# exBoard_2.net
KiCad netlist of a schematic drawn in EasyEDA Pro
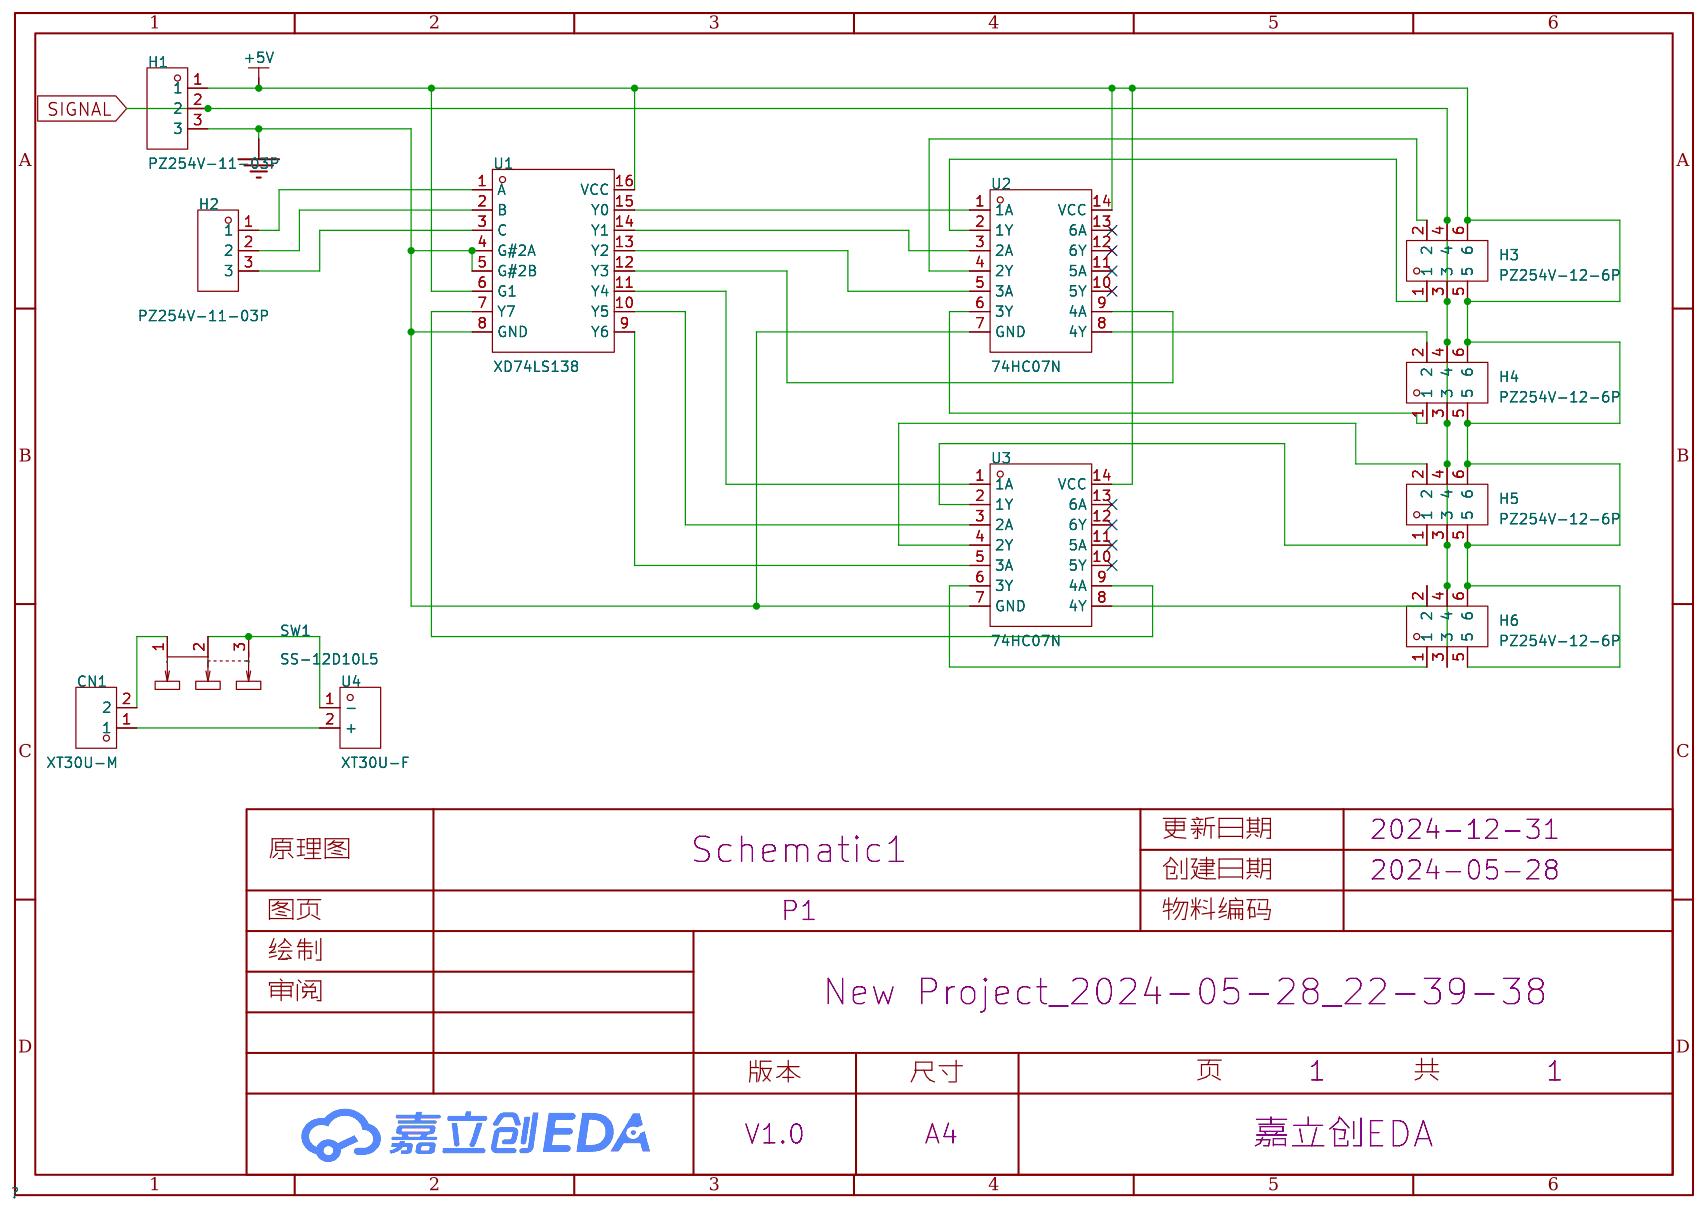
[diagram p0: schematic sheet]

(export (version "E")
  (design (tool "Eeschema 10.0.6"))
  (components
    (comp (ref "CN1")
      (value "XT30U-M")
      (footprint "easyedapro:CONN-TH_XT30U-M")
      (description "类别:-;类型1:-;")
      (fields (field (name "Manufacturer") "AMASS(艾迈斯)"))
      (libsource (lib "easyedapro") (part "XT30U-M"))
    )
    (comp (ref "H1")
      (value "PZ254V-11-03P")
      (footprint "easyedapro:HDR-TH_3P-P2.54-V-M")
      (fields (field (name "Manufacturer") "XFCN(兴飞)"))
      (libsource (lib "easyedapro") (part "PZ254V-11-03P_C2937625"))
    )
    (comp (ref "H2")
      (value "PZ254V-11-03P")
      (footprint "easyedapro:HDR-TH_3P-P2.54-V-M")
      (fields (field (name "Manufacturer") "XFCN(兴飞)"))
      (libsource (lib "easyedapro") (part "PZ254V-11-03P_C2937625"))
    )
    (comp (ref "H3")
      (value "PZ254V-12-6P")
      (footprint "easyedapro:HDR-TH_6P-P2.54-V-M-R2-C3-S2.54")
      (fields (field (name "Manufacturer") "XFCN(兴飞)"))
      (libsource (lib "easyedapro") (part "PZ254V-12-6P"))
    )
    (comp (ref "H4")
      (value "PZ254V-12-6P")
      (footprint "easyedapro:HDR-TH_6P-P2.54-V-M-R2-C3-S2.54")
      (fields (field (name "Manufacturer") "XFCN(兴飞)"))
      (libsource (lib "easyedapro") (part "PZ254V-12-6P"))
    )
    (comp (ref "H5")
      (value "PZ254V-12-6P")
      (footprint "easyedapro:HDR-TH_6P-P2.54-V-M-R2-C3-S2.54")
      (fields (field (name "Manufacturer") "XFCN(兴飞)"))
      (libsource (lib "easyedapro") (part "PZ254V-12-6P"))
    )
    (comp (ref "H6")
      (value "PZ254V-12-6P")
      (footprint "easyedapro:HDR-TH_6P-P2.54-V-M-R2-C3-S2.54")
      (fields (field (name "Manufacturer") "XFCN(兴飞)"))
      (libsource (lib "easyedapro") (part "PZ254V-12-6P"))
    )
    (comp (ref "SW1")
      (value "SS-12D10L5")
      (footprint "easyedapro:SW-TH_SS-12D10L5")
      (description "电路结构:单刀双掷;安装方式:直插;开关颜色:黑色;额定电流(DC):3A;额定电压(DC):125V;额定电流(AC):3A;额定电压(AC):125V;机械寿命:1万次;")
      (fields (field (name "Manufacturer") "XKB Connectivity(中国星坤)"))
      (libsource (lib "easyedapro") (part "SS-12D10L5"))
    )
    (comp (ref "U1")
      (value "XD74LS138")
      (footprint "easyedapro:DIP-16_L19.8-W6.5-P2.54-LS7.6-BL")
      (description "解码器/多路解器 低电平输出电流(IOL)：8mA 高电平输出电流(IOH)：400uA 供电电源：单电源 供电电压：4.75V~5.25V 3 线路到")
      (fields (field (name "Manufacturer") "XINLUDA(信路达)"))
      (libsource (lib "easyedapro") (part "XD74LS138"))
    )
    (comp (ref "U2")
      (value "74HC07N")
      (footprint "easyedapro:DIP-14_L19.4-W6.4-P2.54-LS7.6-BL")
      (fields (field (name "Manufacturer") "HGSEMI(华冠)"))
      (libsource (lib "easyedapro") (part "74HC07N"))
    )
    (comp (ref "U3")
      (value "74HC07N")
      (footprint "easyedapro:DIP-14_L19.4-W6.4-P2.54-LS7.6-BL")
      (fields (field (name "Manufacturer") "HGSEMI(华冠)"))
      (libsource (lib "easyedapro") (part "74HC07N"))
    )
    (comp (ref "U4")
      (value "XT30U-F")
      (footprint "easyedapro:CONN-TH_XT30U-F")
      (description "类别:-;类型1:-;")
      (fields (field (name "Manufacturer") "AMASS(艾迈斯)"))
      (libsource (lib "easyedapro") (part "XT30U-F"))
    )
  )
  (nets
    (net (code "1") (name "+5V") (class "Default")
      (node (ref "H1") (pin "1") (pinfunction "1_1") (pintype "unspecified"))
      (node (ref "H3") (pin "5") (pinfunction "5_5") (pintype "unspecified"))
      (node (ref "H3") (pin "6") (pinfunction "6_6") (pintype "unspecified"))
      (node (ref "H4") (pin "5") (pinfunction "5_5") (pintype "unspecified"))
      (node (ref "H4") (pin "6") (pinfunction "6_6") (pintype "unspecified"))
      (node (ref "H5") (pin "5") (pinfunction "5_5") (pintype "unspecified"))
      (node (ref "H5") (pin "6") (pinfunction "6_6") (pintype "unspecified"))
      (node (ref "H6") (pin "5") (pinfunction "5_5") (pintype "unspecified"))
      (node (ref "H6") (pin "6") (pinfunction "6_6") (pintype "unspecified"))
      (node (ref "U1") (pin "16") (pinfunction "VCC_16") (pintype "unspecified"))
      (node (ref "U1") (pin "6") (pinfunction "G1_6") (pintype "unspecified"))
      (node (ref "U2") (pin "14") (pinfunction "VCC_14") (pintype "unspecified"))
      (node (ref "U3") (pin "14") (pinfunction "VCC_14") (pintype "unspecified"))
    )
    (net (code "2") (name "GND") (class "Default")
      (node (ref "H1") (pin "3") (pinfunction "3_3") (pintype "unspecified"))
      (node (ref "U1") (pin "4") (pinfunction "G#2A_4") (pintype "unspecified"))
      (node (ref "U1") (pin "5") (pinfunction "G#2B_5") (pintype "unspecified"))
      (node (ref "U1") (pin "8") (pinfunction "GND_8") (pintype "unspecified"))
      (node (ref "U2") (pin "7") (pinfunction "GND_7") (pintype "unspecified"))
      (node (ref "U3") (pin "7") (pinfunction "GND_7") (pintype "unspecified"))
    )
    (net (code "3") (name "Net-(CN1-Pad2)") (class "Default")
      (node (ref "CN1") (pin "2") (pinfunction "2_2") (pintype "input"))
      (node (ref "SW1") (pin "1") (pinfunction "1_1") (pintype "unspecified"))
    )
    (net (code "4") (name "Net-(U1-A)") (class "Default")
      (node (ref "H2") (pin "1") (pinfunction "1_1") (pintype "unspecified"))
      (node (ref "U1") (pin "1") (pinfunction "A_1") (pintype "unspecified"))
    )
    (net (code "5") (name "Net-(U1-B)") (class "Default")
      (node (ref "H2") (pin "2") (pinfunction "2_2") (pintype "unspecified"))
      (node (ref "U1") (pin "2") (pinfunction "B_2") (pintype "unspecified"))
    )
    (net (code "6") (name "Net-(U1-C)") (class "Default")
      (node (ref "H2") (pin "3") (pinfunction "3_3") (pintype "unspecified"))
      (node (ref "U1") (pin "3") (pinfunction "C_3") (pintype "unspecified"))
    )
    (net (code "7") (name "Net-(U1-Y0)") (class "Default")
      (node (ref "U1") (pin "15") (pinfunction "Y0_15") (pintype "unspecified"))
      (node (ref "U2") (pin "1") (pinfunction "1A_1") (pintype "unspecified"))
    )
    (net (code "8") (name "Net-(U1-Y1)") (class "Default")
      (node (ref "U1") (pin "14") (pinfunction "Y1_14") (pintype "unspecified"))
      (node (ref "U2") (pin "3") (pinfunction "2A_3") (pintype "unspecified"))
    )
    (net (code "9") (name "Net-(U1-Y2)") (class "Default")
      (node (ref "U1") (pin "13") (pinfunction "Y2_13") (pintype "unspecified"))
      (node (ref "U2") (pin "5") (pinfunction "3A_5") (pintype "unspecified"))
    )
    (net (code "10") (name "Net-(U1-Y3)") (class "Default")
      (node (ref "U1") (pin "12") (pinfunction "Y3_12") (pintype "unspecified"))
      (node (ref "U2") (pin "9") (pinfunction "4A_9") (pintype "unspecified"))
    )
    (net (code "11") (name "Net-(U1-Y4)") (class "Default")
      (node (ref "U1") (pin "11") (pinfunction "Y4_11") (pintype "unspecified"))
      (node (ref "U3") (pin "1") (pinfunction "1A_1") (pintype "unspecified"))
    )
    (net (code "12") (name "Net-(U1-Y5)") (class "Default")
      (node (ref "U1") (pin "10") (pinfunction "Y5_10") (pintype "unspecified"))
      (node (ref "U3") (pin "3") (pinfunction "2A_3") (pintype "unspecified"))
    )
    (net (code "13") (name "Net-(U1-Y6)") (class "Default")
      (node (ref "U1") (pin "9") (pinfunction "Y6_9") (pintype "unspecified"))
      (node (ref "U3") (pin "5") (pinfunction "3A_5") (pintype "unspecified"))
    )
    (net (code "14") (name "Net-(U1-Y7)") (class "Default")
      (node (ref "U1") (pin "7") (pinfunction "Y7_7") (pintype "unspecified"))
      (node (ref "U3") (pin "9") (pinfunction "4A_9") (pintype "unspecified"))
    )
    (net (code "15") (name "Net-(U2-1Y)") (class "Default")
      (node (ref "H3") (pin "1") (pinfunction "1_1") (pintype "unspecified"))
      (node (ref "U2") (pin "2") (pinfunction "1Y_2") (pintype "unspecified"))
    )
    (net (code "16") (name "Net-(U2-2Y)") (class "Default")
      (node (ref "H3") (pin "2") (pinfunction "2_2") (pintype "unspecified"))
      (node (ref "U2") (pin "4") (pinfunction "2Y_4") (pintype "unspecified"))
    )
    (net (code "17") (name "Net-(U2-3Y)") (class "Default")
      (node (ref "H4") (pin "1") (pinfunction "1_1") (pintype "unspecified"))
      (node (ref "U2") (pin "6") (pinfunction "3Y_6") (pintype "unspecified"))
    )
    (net (code "18") (name "Net-(U2-4Y)") (class "Default")
      (node (ref "H4") (pin "2") (pinfunction "2_2") (pintype "unspecified"))
      (node (ref "U2") (pin "8") (pinfunction "4Y_8") (pintype "unspecified"))
    )
    (net (code "19") (name "Net-(U3-1Y)") (class "Default")
      (node (ref "H5") (pin "1") (pinfunction "1_1") (pintype "unspecified"))
      (node (ref "U3") (pin "2") (pinfunction "1Y_2") (pintype "unspecified"))
    )
    (net (code "20") (name "Net-(U3-2Y)") (class "Default")
      (node (ref "H5") (pin "2") (pinfunction "2_2") (pintype "unspecified"))
      (node (ref "U3") (pin "4") (pinfunction "2Y_4") (pintype "unspecified"))
    )
    (net (code "21") (name "Net-(U3-3Y)") (class "Default")
      (node (ref "H6") (pin "1") (pinfunction "1_1") (pintype "unspecified"))
      (node (ref "U3") (pin "6") (pinfunction "3Y_6") (pintype "unspecified"))
    )
    (net (code "22") (name "Net-(U3-4Y)") (class "Default")
      (node (ref "H6") (pin "2") (pinfunction "2_2") (pintype "unspecified"))
      (node (ref "U3") (pin "8") (pinfunction "4Y_8") (pintype "unspecified"))
    )
    (net (code "23") (name "Net-(U4-+)") (class "Default")
      (node (ref "CN1") (pin "1") (pinfunction "1_1") (pintype "input"))
      (node (ref "U4") (pin "2") (pinfunction "+_2") (pintype "unspecified"))
    )
    (net (code "24") (name "Net-(U4--)") (class "Default")
      (node (ref "SW1") (pin "2") (pinfunction "2_2") (pintype "unspecified"))
      (node (ref "SW1") (pin "3") (pinfunction "3_3") (pintype "unspecified"))
      (node (ref "U4") (pin "1") (pinfunction "-_1") (pintype "unspecified"))
    )
    (net (code "25") (name "SIGNAL") (class "Default")
      (node (ref "H1") (pin "2") (pinfunction "2_2") (pintype "unspecified"))
      (node (ref "H3") (pin "3") (pinfunction "3_3") (pintype "unspecified"))
      (node (ref "H3") (pin "4") (pinfunction "4_4") (pintype "unspecified"))
      (node (ref "H4") (pin "3") (pinfunction "3_3") (pintype "unspecified"))
      (node (ref "H4") (pin "4") (pinfunction "4_4") (pintype "unspecified"))
      (node (ref "H5") (pin "3") (pinfunction "3_3") (pintype "unspecified"))
      (node (ref "H5") (pin "4") (pinfunction "4_4") (pintype "unspecified"))
      (node (ref "H6") (pin "3") (pinfunction "3_3") (pintype "unspecified"))
      (node (ref "H6") (pin "4") (pinfunction "4_4") (pintype "unspecified"))
    )
    (net (code "26") (name "unconnected-(U2-5A-Pad11)") (class "Default")
      (node (ref "U2") (pin "11") (pinfunction "5A_11") (pintype "unspecified+no_connect"))
    )
    (net (code "27") (name "unconnected-(U2-5Y-Pad10)") (class "Default")
      (node (ref "U2") (pin "10") (pinfunction "5Y_10") (pintype "unspecified+no_connect"))
    )
    (net (code "28") (name "unconnected-(U2-6A-Pad13)") (class "Default")
      (node (ref "U2") (pin "13") (pinfunction "6A_13") (pintype "unspecified+no_connect"))
    )
    (net (code "29") (name "unconnected-(U2-6Y-Pad12)") (class "Default")
      (node (ref "U2") (pin "12") (pinfunction "6Y_12") (pintype "unspecified+no_connect"))
    )
    (net (code "30") (name "unconnected-(U3-5A-Pad11)") (class "Default")
      (node (ref "U3") (pin "11") (pinfunction "5A_11") (pintype "unspecified+no_connect"))
    )
    (net (code "31") (name "unconnected-(U3-5Y-Pad10)") (class "Default")
      (node (ref "U3") (pin "10") (pinfunction "5Y_10") (pintype "unspecified+no_connect"))
    )
    (net (code "32") (name "unconnected-(U3-6A-Pad13)") (class "Default")
      (node (ref "U3") (pin "13") (pinfunction "6A_13") (pintype "unspecified+no_connect"))
    )
    (net (code "33") (name "unconnected-(U3-6Y-Pad12)") (class "Default")
      (node (ref "U3") (pin "12") (pinfunction "6Y_12") (pintype "unspecified+no_connect"))
    )
  )
)
